# KA2_3.net
KiCad netlist of a schematic drawn in Altium Designer
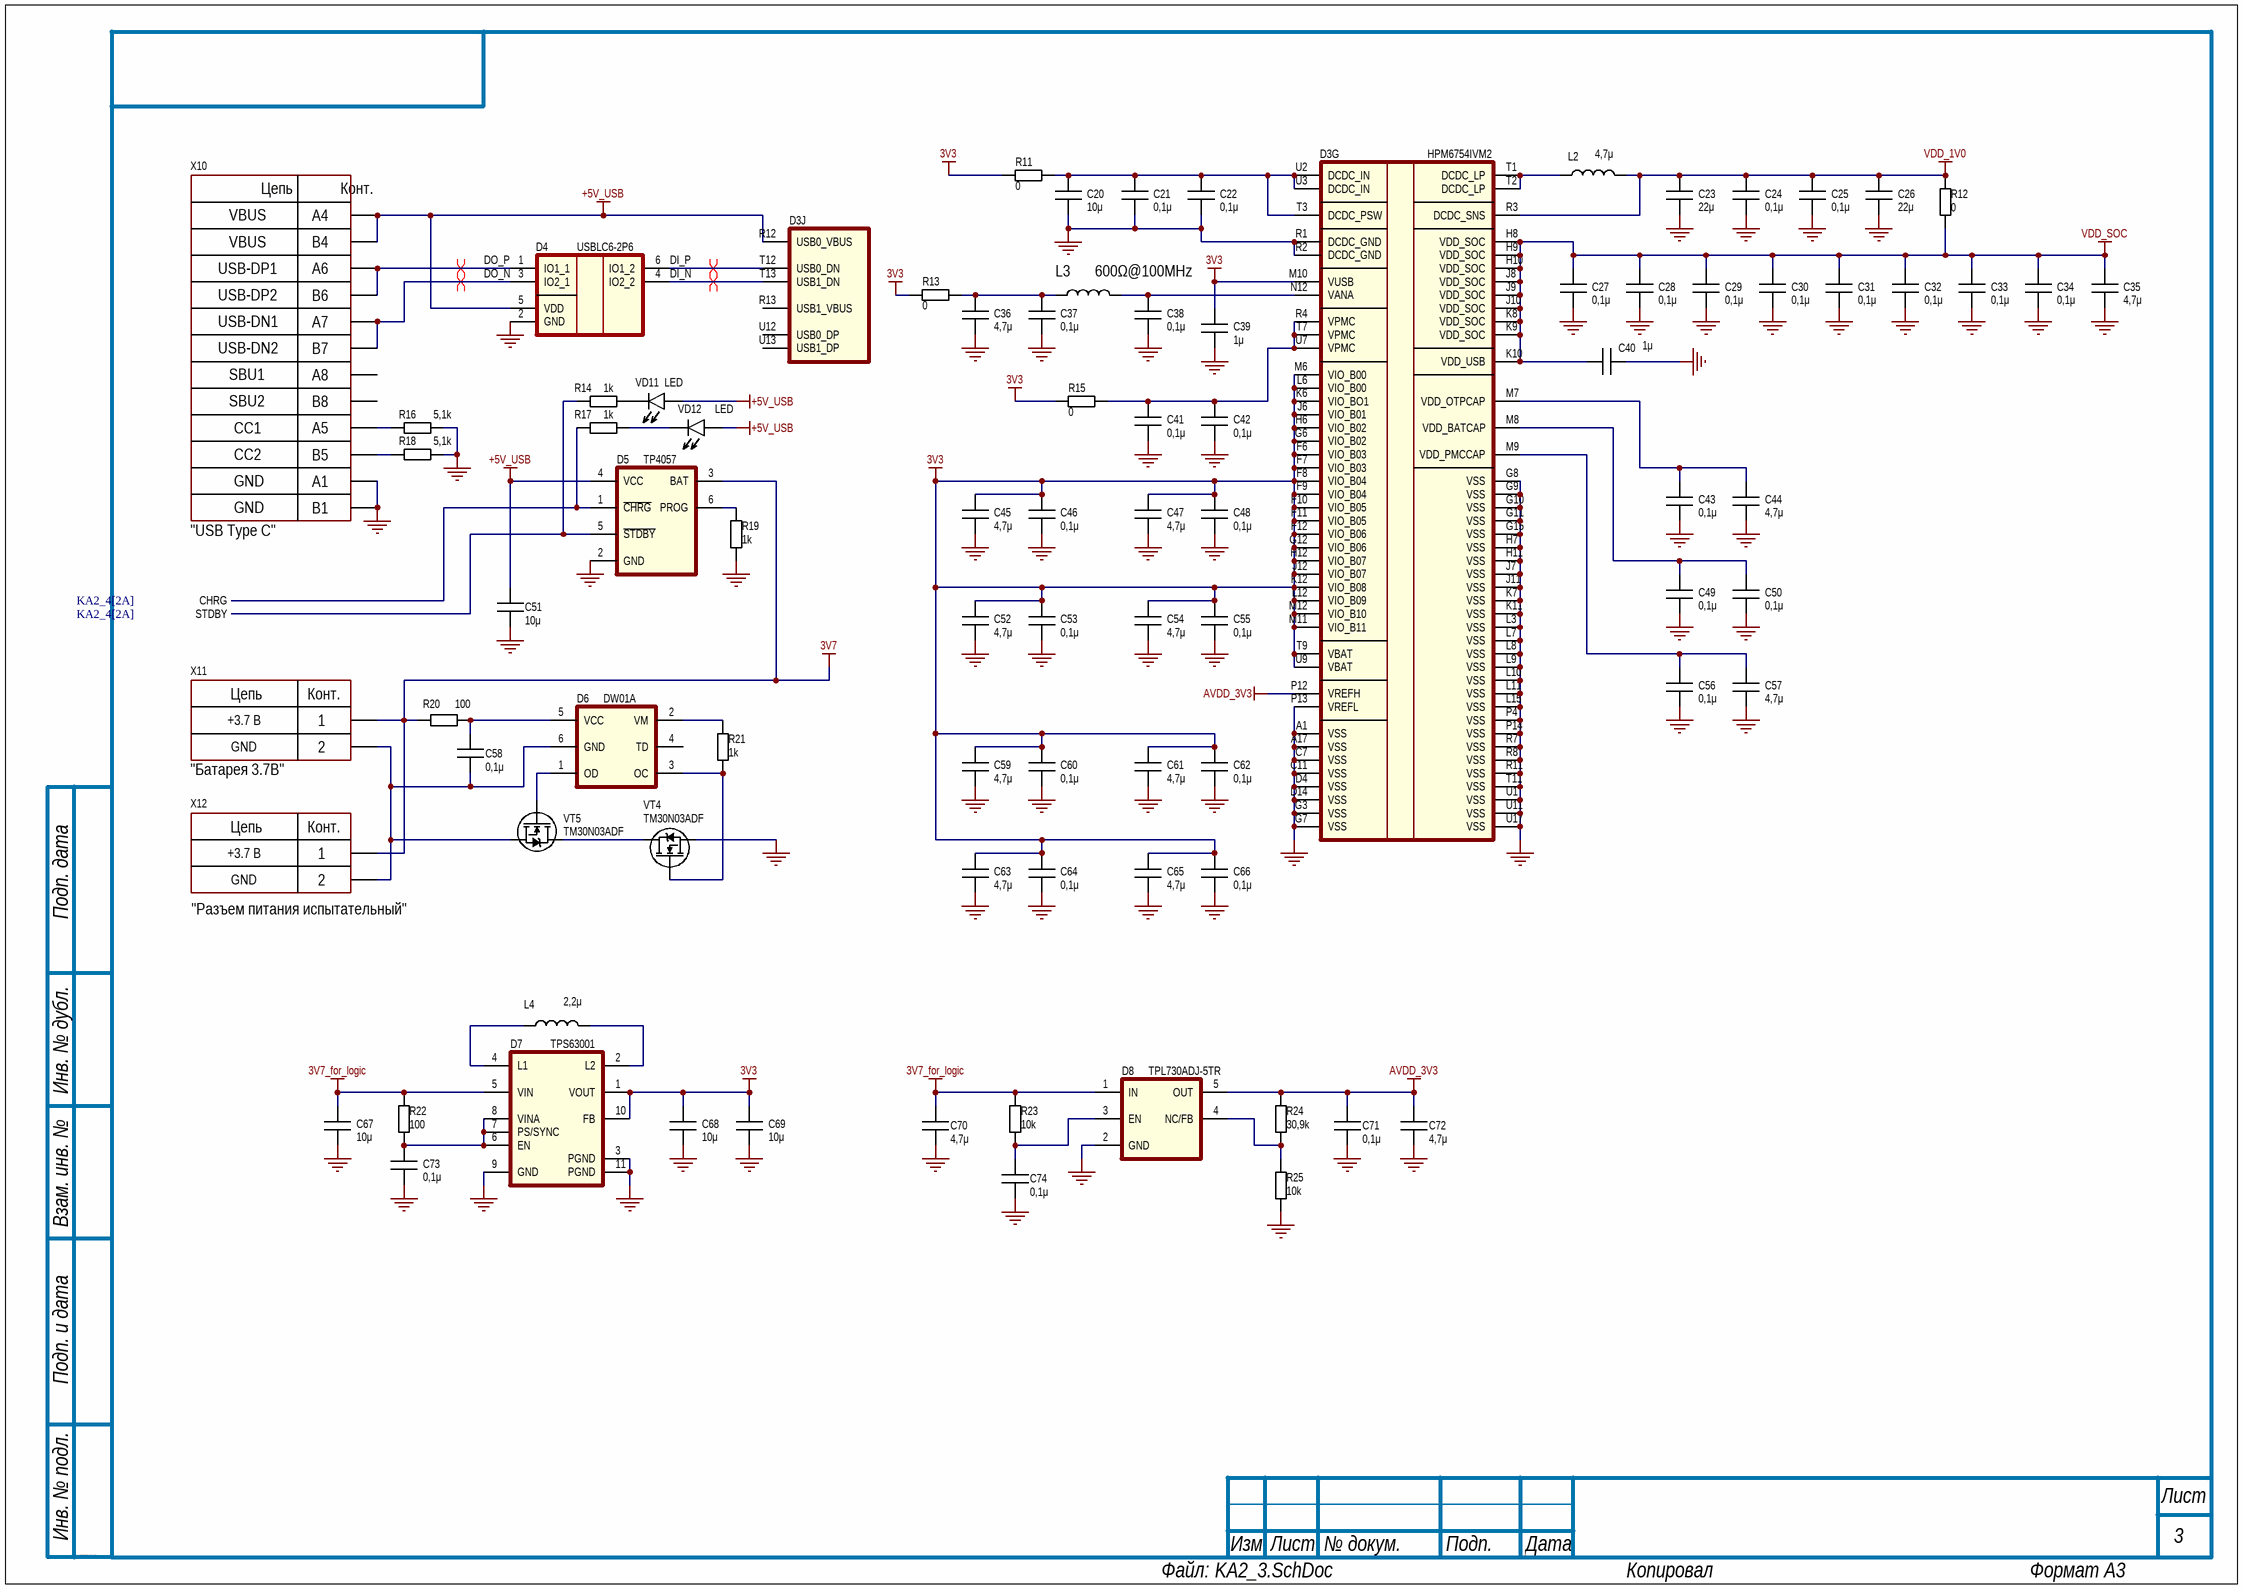
[diagram p0: KA2_3.SchDoc]

(export (version "E")
  (design (tool "Eeschema 10.0.6"))
  (components
    (comp (ref "C20")
      (value "10μ")
      (footprint "Capacitor_0402")
      (fields
        (field (name "VALUEMANUFACTURERPARTNUMBER") "Ceramic capacitor, 10μ, X7R, ±10%, 16V, 0402")
        (field (name "TOLERANCE") "±10%")
        (field (name "VOLTAGE") "16V")
      )
      (libsource (lib "Barsotion") (part "Ceramic_0402"))
    )
    (comp (ref "C21")
      (value "0,1μ")
      (footprint "Capacitor_0402")
      (fields
        (field (name "VALUEMANUFACTURERPARTNUMBER") "Ceramic capacitor, 0,1μ, X7R, ±10%, 16V, 0402")
        (field (name "TOLERANCE") "±10%")
        (field (name "VOLTAGE") "16V")
      )
      (libsource (lib "Barsotion") (part "Ceramic_0402"))
    )
    (comp (ref "C22")
      (value "0,1μ")
      (footprint "Capacitor_0402")
      (fields
        (field (name "VALUEMANUFACTURERPARTNUMBER") "Ceramic capacitor, 0,1μ, X7R, ±10%, 16V, 0402")
        (field (name "TOLERANCE") "±10%")
        (field (name "VOLTAGE") "16V")
      )
      (libsource (lib "Barsotion") (part "Ceramic_0402"))
    )
    (comp (ref "C23")
      (value "22μ")
      (footprint "Capacitor_0402")
      (fields
        (field (name "VALUEMANUFACTURERPARTNUMBER") "Ceramic capacitor, 22μ, X7R, ±10%, 16V, 0402")
        (field (name "TOLERANCE") "±10%")
        (field (name "VOLTAGE") "16V")
      )
      (libsource (lib "Barsotion") (part "Ceramic_0402"))
    )
    (comp (ref "C24")
      (value "0,1μ")
      (footprint "Capacitor_0402")
      (fields
        (field (name "VALUEMANUFACTURERPARTNUMBER") "Ceramic capacitor, 0,1μ, X7R, ±10%, 16V, 0402")
        (field (name "TOLERANCE") "±10%")
        (field (name "VOLTAGE") "16V")
      )
      (libsource (lib "Barsotion") (part "Ceramic_0402"))
    )
    (comp (ref "C25")
      (value "0,1μ")
      (footprint "Capacitor_0402")
      (fields
        (field (name "VALUEMANUFACTURERPARTNUMBER") "Ceramic capacitor, 0,1μ, X7R, ±10%, 16V, 0402")
        (field (name "TOLERANCE") "±10%")
        (field (name "VOLTAGE") "16V")
      )
      (libsource (lib "Barsotion") (part "Ceramic_0402"))
    )
    (comp (ref "C26")
      (value "22μ")
      (footprint "Capacitor_0402")
      (fields
        (field (name "VALUEMANUFACTURERPARTNUMBER") "Ceramic capacitor, 22μ, X7R, ±10%, 16V, 0402")
        (field (name "TOLERANCE") "±10%")
        (field (name "VOLTAGE") "16V")
      )
      (libsource (lib "Barsotion") (part "Ceramic_0402"))
    )
    (comp (ref "C27")
      (value "0,1μ")
      (footprint "Capacitor_0402")
      (fields
        (field (name "VALUEMANUFACTURERPARTNUMBER") "Ceramic capacitor, 0,1μ, X7R, ±10%, 16V, 0402")
        (field (name "TOLERANCE") "±10%")
        (field (name "VOLTAGE") "16V")
      )
      (libsource (lib "Barsotion") (part "Ceramic_0402"))
    )
    (comp (ref "C28")
      (value "0,1μ")
      (footprint "Capacitor_0402")
      (fields
        (field (name "VALUEMANUFACTURERPARTNUMBER") "Ceramic capacitor, 0,1μ, X7R, ±10%, 16V, 0402")
        (field (name "TOLERANCE") "±10%")
        (field (name "VOLTAGE") "16V")
      )
      (libsource (lib "Barsotion") (part "Ceramic_0402"))
    )
    (comp (ref "C29")
      (value "0,1μ")
      (footprint "Capacitor_0402")
      (fields
        (field (name "VALUEMANUFACTURERPARTNUMBER") "Ceramic capacitor, 0,1μ, X7R, ±10%, 16V, 0402")
        (field (name "TOLERANCE") "±10%")
        (field (name "VOLTAGE") "16V")
      )
      (libsource (lib "Barsotion") (part "Ceramic_0402"))
    )
    (comp (ref "C30")
      (value "0,1μ")
      (footprint "Capacitor_0402")
      (fields
        (field (name "VALUEMANUFACTURERPARTNUMBER") "Ceramic capacitor, 0,1μ, X7R, ±10%, 16V, 0402")
        (field (name "TOLERANCE") "±10%")
        (field (name "VOLTAGE") "16V")
      )
      (libsource (lib "Barsotion") (part "Ceramic_0402"))
    )
    (comp (ref "C31")
      (value "0,1μ")
      (footprint "Capacitor_0402")
      (fields
        (field (name "VALUEMANUFACTURERPARTNUMBER") "Ceramic capacitor, 0,1μ, X7R, ±10%, 16V, 0402")
        (field (name "TOLERANCE") "±10%")
        (field (name "VOLTAGE") "16V")
      )
      (libsource (lib "Barsotion") (part "Ceramic_0402"))
    )
    (comp (ref "C32")
      (value "0,1μ")
      (footprint "Capacitor_0402")
      (fields
        (field (name "VALUEMANUFACTURERPARTNUMBER") "Ceramic capacitor, 0,1μ, X7R, ±10%, 16V, 0402")
        (field (name "TOLERANCE") "±10%")
        (field (name "VOLTAGE") "16V")
      )
      (libsource (lib "Barsotion") (part "Ceramic_0402"))
    )
    (comp (ref "C33")
      (value "0,1μ")
      (footprint "Capacitor_0402")
      (fields
        (field (name "VALUEMANUFACTURERPARTNUMBER") "Ceramic capacitor, 0,1μ, X7R, ±10%, 16V, 0402")
        (field (name "TOLERANCE") "±10%")
        (field (name "VOLTAGE") "16V")
      )
      (libsource (lib "Barsotion") (part "Ceramic_0402"))
    )
    (comp (ref "C34")
      (value "0,1μ")
      (footprint "Capacitor_0402")
      (fields
        (field (name "VALUEMANUFACTURERPARTNUMBER") "Ceramic capacitor, 0,1μ, X7R, ±10%, 16V, 0402")
        (field (name "TOLERANCE") "±10%")
        (field (name "VOLTAGE") "16V")
      )
      (libsource (lib "Barsotion") (part "Ceramic_0402"))
    )
    (comp (ref "C35")
      (value "4,7μ")
      (footprint "Capacitor_0402")
      (fields
        (field (name "VALUEMANUFACTURERPARTNUMBER") "Ceramic capacitor, 4,7μ, X7R, ±10%, 16V, 0402")
        (field (name "TOLERANCE") "±10%")
        (field (name "VOLTAGE") "16V")
      )
      (libsource (lib "Barsotion") (part "Ceramic_0402"))
    )
    (comp (ref "C36")
      (value "4,7μ")
      (footprint "Capacitor_0402")
      (fields
        (field (name "VALUEMANUFACTURERPARTNUMBER") "Ceramic capacitor, 4,7μ, X7R, ±10%, 16V, 0402")
        (field (name "TOLERANCE") "±10%")
        (field (name "VOLTAGE") "16V")
      )
      (libsource (lib "Barsotion") (part "Ceramic_0402"))
    )
    (comp (ref "C37")
      (value "0,1μ")
      (footprint "Capacitor_0402")
      (fields
        (field (name "VALUEMANUFACTURERPARTNUMBER") "Ceramic capacitor, 0,1μ, X7R, ±10%, 16V, 0402")
        (field (name "TOLERANCE") "±10%")
        (field (name "VOLTAGE") "16V")
      )
      (libsource (lib "Barsotion") (part "Ceramic_0402"))
    )
    (comp (ref "C38")
      (value "0,1μ")
      (footprint "Capacitor_0402")
      (fields
        (field (name "VALUEMANUFACTURERPARTNUMBER") "Ceramic capacitor, 0,1μ, X7R, ±10%, 16V, 0402")
        (field (name "TOLERANCE") "±10%")
        (field (name "VOLTAGE") "16V")
      )
      (libsource (lib "Barsotion") (part "Ceramic_0402"))
    )
    (comp (ref "C39")
      (value "1μ")
      (footprint "Capacitor_0402")
      (fields
        (field (name "VALUEMANUFACTURERPARTNUMBER") "Ceramic capacitor, 1μ, X7R, ±10%, 16V, 0402")
        (field (name "TOLERANCE") "±10%")
        (field (name "VOLTAGE") "16V")
      )
      (libsource (lib "Barsotion") (part "Ceramic_0402"))
    )
    (comp (ref "C40")
      (value "1μ")
      (footprint "Capacitor_0402")
      (fields
        (field (name "VALUEMANUFACTURERPARTNUMBER") "Ceramic capacitor, 1μ, X7R, ±10%, 16V, 0402")
        (field (name "TOLERANCE") "±10%")
        (field (name "VOLTAGE") "16V")
      )
      (libsource (lib "Barsotion") (part "Ceramic_0402"))
    )
    (comp (ref "C41")
      (value "0,1μ")
      (footprint "Capacitor_0402")
      (fields
        (field (name "VALUEMANUFACTURERPARTNUMBER") "Ceramic capacitor, 0,1μ, X7R, ±10%, 16V, 0402")
        (field (name "TOLERANCE") "±10%")
        (field (name "VOLTAGE") "16V")
      )
      (libsource (lib "Barsotion") (part "Ceramic_0402"))
    )
    (comp (ref "C42")
      (value "0,1μ")
      (footprint "Capacitor_0402")
      (fields
        (field (name "VALUEMANUFACTURERPARTNUMBER") "Ceramic capacitor, 0,1μ, X7R, ±10%, 16V, 0402")
        (field (name "TOLERANCE") "±10%")
        (field (name "VOLTAGE") "16V")
      )
      (libsource (lib "Barsotion") (part "Ceramic_0402"))
    )
    (comp (ref "C43")
      (value "0,1μ")
      (footprint "Capacitor_0402")
      (fields
        (field (name "VALUEMANUFACTURERPARTNUMBER") "Ceramic capacitor, 0,1μ, X7R, ±10%, 16V, 0402")
        (field (name "TOLERANCE") "±10%")
        (field (name "VOLTAGE") "16V")
      )
      (libsource (lib "Barsotion") (part "Ceramic_0402"))
    )
    (comp (ref "C44")
      (value "4,7μ")
      (footprint "Capacitor_0402")
      (fields
        (field (name "VALUEMANUFACTURERPARTNUMBER") "Ceramic capacitor, 4,7μ, X7R, ±10%, 16V, 0402")
        (field (name "TOLERANCE") "±10%")
        (field (name "VOLTAGE") "16V")
      )
      (libsource (lib "Barsotion") (part "Ceramic_0402"))
    )
    (comp (ref "C45")
      (value "4,7μ")
      (footprint "Capacitor_0402")
      (fields
        (field (name "VALUEMANUFACTURERPARTNUMBER") "Ceramic capacitor, 4,7μ, X7R, ±10%, 16V, 0402")
        (field (name "TOLERANCE") "±10%")
        (field (name "VOLTAGE") "16V")
      )
      (libsource (lib "Barsotion") (part "Ceramic_0402"))
    )
    (comp (ref "C46")
      (value "0,1μ")
      (footprint "Capacitor_0402")
      (fields
        (field (name "VALUEMANUFACTURERPARTNUMBER") "Ceramic capacitor, 0,1μ, X7R, ±10%, 16V, 0402")
        (field (name "TOLERANCE") "±10%")
        (field (name "VOLTAGE") "16V")
      )
      (libsource (lib "Barsotion") (part "Ceramic_0402"))
    )
    (comp (ref "C47")
      (value "4,7μ")
      (footprint "Capacitor_0402")
      (fields
        (field (name "VALUEMANUFACTURERPARTNUMBER") "Ceramic capacitor, 4,7μ, X7R, ±10%, 16V, 0402")
        (field (name "TOLERANCE") "±10%")
        (field (name "VOLTAGE") "16V")
      )
      (libsource (lib "Barsotion") (part "Ceramic_0402"))
    )
    (comp (ref "C48")
      (value "0,1μ")
      (footprint "Capacitor_0402")
      (fields
        (field (name "VALUEMANUFACTURERPARTNUMBER") "Ceramic capacitor, 0,1μ, X7R, ±10%, 16V, 0402")
        (field (name "TOLERANCE") "±10%")
        (field (name "VOLTAGE") "16V")
      )
      (libsource (lib "Barsotion") (part "Ceramic_0402"))
    )
    (comp (ref "C49")
      (value "0,1μ")
      (footprint "Capacitor_0402")
      (fields
        (field (name "VALUEMANUFACTURERPARTNUMBER") "Ceramic capacitor, 0,1μ, X7R, ±10%, 16V, 0402")
        (field (name "TOLERANCE") "±10%")
        (field (name "VOLTAGE") "16V")
      )
      (libsource (lib "Barsotion") (part "Ceramic_0402"))
    )
    (comp (ref "C50")
      (value "0,1μ")
      (footprint "Capacitor_0402")
      (fields
        (field (name "VALUEMANUFACTURERPARTNUMBER") "Ceramic capacitor, 0,1μ, X7R, ±10%, 16V, 0402")
        (field (name "TOLERANCE") "±10%")
        (field (name "VOLTAGE") "16V")
      )
      (libsource (lib "Barsotion") (part "Ceramic_0402"))
    )
    (comp (ref "C51")
      (value "10μ")
      (footprint "Capacitor_0402")
      (fields
        (field (name "VALUEMANUFACTURERPARTNUMBER") "Ceramic capacitor, 10μ, X7R, ±10%, 16V, 0402")
        (field (name "TOLERANCE") "±10%")
        (field (name "VOLTAGE") "16V")
      )
      (libsource (lib "Barsotion") (part "Ceramic_0402"))
    )
    (comp (ref "C52")
      (value "4,7μ")
      (footprint "Capacitor_0402")
      (fields
        (field (name "VALUEMANUFACTURERPARTNUMBER") "Ceramic capacitor, 4,7μ, X7R, ±10%, 16V, 0402")
        (field (name "TOLERANCE") "±10%")
        (field (name "VOLTAGE") "16V")
      )
      (libsource (lib "Barsotion") (part "Ceramic_0402"))
    )
    (comp (ref "C53")
      (value "0,1μ")
      (footprint "Capacitor_0402")
      (fields
        (field (name "VALUEMANUFACTURERPARTNUMBER") "Ceramic capacitor, 0,1μ, X7R, ±10%, 16V, 0402")
        (field (name "TOLERANCE") "±10%")
        (field (name "VOLTAGE") "16V")
      )
      (libsource (lib "Barsotion") (part "Ceramic_0402"))
    )
    (comp (ref "C54")
      (value "4,7μ")
      (footprint "Capacitor_0402")
      (fields
        (field (name "VALUEMANUFACTURERPARTNUMBER") "Ceramic capacitor, 4,7μ, X7R, ±10%, 16V, 0402")
        (field (name "TOLERANCE") "±10%")
        (field (name "VOLTAGE") "16V")
      )
      (libsource (lib "Barsotion") (part "Ceramic_0402"))
    )
    (comp (ref "C55")
      (value "0,1μ")
      (footprint "Capacitor_0402")
      (fields
        (field (name "VALUEMANUFACTURERPARTNUMBER") "Ceramic capacitor, 0,1μ, X7R, ±10%, 16V, 0402")
        (field (name "TOLERANCE") "±10%")
        (field (name "VOLTAGE") "16V")
      )
      (libsource (lib "Barsotion") (part "Ceramic_0402"))
    )
    (comp (ref "C56")
      (value "0,1μ")
      (footprint "Capacitor_0402")
      (fields
        (field (name "VALUEMANUFACTURERPARTNUMBER") "Ceramic capacitor, 0,1μ, X7R, ±10%, 16V, 0402")
        (field (name "TOLERANCE") "±10%")
        (field (name "VOLTAGE") "16V")
      )
      (libsource (lib "Barsotion") (part "Ceramic_0402"))
    )
    (comp (ref "C57")
      (value "4,7μ")
      (footprint "Capacitor_0402")
      (fields
        (field (name "VALUEMANUFACTURERPARTNUMBER") "Ceramic capacitor, 4,7μ, X7R, ±10%, 16V, 0402")
        (field (name "TOLERANCE") "±10%")
        (field (name "VOLTAGE") "16V")
      )
      (libsource (lib "Barsotion") (part "Ceramic_0402"))
    )
    (comp (ref "C58")
      (value "0,1μ")
      (footprint "Capacitor_0402")
      (fields
        (field (name "VALUEMANUFACTURERPARTNUMBER") "Ceramic capacitor, 0,1μ, X7R, ±10%, 16V, 0402")
        (field (name "TOLERANCE") "±10%")
        (field (name "VOLTAGE") "16V")
      )
      (libsource (lib "Barsotion") (part "Ceramic_0402"))
    )
    (comp (ref "C59")
      (value "4,7μ")
      (footprint "Capacitor_0402")
      (fields
        (field (name "VALUEMANUFACTURERPARTNUMBER") "Ceramic capacitor, 4,7μ, X7R, ±10%, 16V, 0402")
        (field (name "TOLERANCE") "±10%")
        (field (name "VOLTAGE") "16V")
      )
      (libsource (lib "Barsotion") (part "Ceramic_0402"))
    )
    (comp (ref "C60")
      (value "0,1μ")
      (footprint "Capacitor_0402")
      (fields
        (field (name "VALUEMANUFACTURERPARTNUMBER") "Ceramic capacitor, 0,1μ, X7R, ±10%, 16V, 0402")
        (field (name "TOLERANCE") "±10%")
        (field (name "VOLTAGE") "16V")
      )
      (libsource (lib "Barsotion") (part "Ceramic_0402"))
    )
    (comp (ref "C61")
      (value "4,7μ")
      (footprint "Capacitor_0402")
      (fields
        (field (name "VALUEMANUFACTURERPARTNUMBER") "Ceramic capacitor, 4,7μ, X7R, ±10%, 16V, 0402")
        (field (name "TOLERANCE") "±10%")
        (field (name "VOLTAGE") "16V")
      )
      (libsource (lib "Barsotion") (part "Ceramic_0402"))
    )
    (comp (ref "C62")
      (value "0,1μ")
      (footprint "Capacitor_0402")
      (fields
        (field (name "VALUEMANUFACTURERPARTNUMBER") "Ceramic capacitor, 0,1μ, X7R, ±10%, 16V, 0402")
        (field (name "TOLERANCE") "±10%")
        (field (name "VOLTAGE") "16V")
      )
      (libsource (lib "Barsotion") (part "Ceramic_0402"))
    )
    (comp (ref "C63")
      (value "4,7μ")
      (footprint "Capacitor_0402")
      (fields
        (field (name "VALUEMANUFACTURERPARTNUMBER") "Ceramic capacitor, 4,7μ, X7R, ±10%, 16V, 0402")
        (field (name "TOLERANCE") "±10%")
        (field (name "VOLTAGE") "16V")
      )
      (libsource (lib "Barsotion") (part "Ceramic_0402"))
    )
    (comp (ref "C64")
      (value "0,1μ")
      (footprint "Capacitor_0402")
      (fields
        (field (name "VALUEMANUFACTURERPARTNUMBER") "Ceramic capacitor, 0,1μ, X7R, ±10%, 16V, 0402")
        (field (name "TOLERANCE") "±10%")
        (field (name "VOLTAGE") "16V")
      )
      (libsource (lib "Barsotion") (part "Ceramic_0402"))
    )
    (comp (ref "C65")
      (value "4,7μ")
      (footprint "Capacitor_0402")
      (fields
        (field (name "VALUEMANUFACTURERPARTNUMBER") "Ceramic capacitor, 4,7μ, X7R, ±10%, 16V, 0402")
        (field (name "TOLERANCE") "±10%")
        (field (name "VOLTAGE") "16V")
      )
      (libsource (lib "Barsotion") (part "Ceramic_0402"))
    )
    (comp (ref "C66")
      (value "0,1μ")
      (footprint "Capacitor_0402")
      (fields
        (field (name "VALUEMANUFACTURERPARTNUMBER") "Ceramic capacitor, 0,1μ, X7R, ±10%, 16V, 0402")
        (field (name "TOLERANCE") "±10%")
        (field (name "VOLTAGE") "16V")
      )
      (libsource (lib "Barsotion") (part "Ceramic_0402"))
    )
    (comp (ref "C67")
      (value "10μ")
      (footprint "Capacitor_0402")
      (fields
        (field (name "VALUEMANUFACTURERPARTNUMBER") "Ceramic capacitor, 10μ, X7R, ±10%, 16V, 0402")
        (field (name "TOLERANCE") "±10%")
        (field (name "VOLTAGE") "16V")
      )
      (libsource (lib "Barsotion") (part "Ceramic_0402"))
    )
    (comp (ref "C68")
      (value "10μ")
      (footprint "Capacitor_0402")
      (fields
        (field (name "VALUEMANUFACTURERPARTNUMBER") "Ceramic capacitor, 10μ, X7R, ±10%, 16V, 0402")
        (field (name "TOLERANCE") "±10%")
        (field (name "VOLTAGE") "16V")
      )
      (libsource (lib "Barsotion") (part "Ceramic_0402"))
    )
    (comp (ref "C69")
      (value "10μ")
      (footprint "Capacitor_0402")
      (fields
        (field (name "VALUEMANUFACTURERPARTNUMBER") "Ceramic capacitor, 10μ, X7R, ±10%, 16V, 0402")
        (field (name "TOLERANCE") "±10%")
        (field (name "VOLTAGE") "16V")
      )
      (libsource (lib "Barsotion") (part "Ceramic_0402"))
    )
    (comp (ref "C70")
      (value "4,7μ")
      (footprint "Capacitor_0402")
      (fields
        (field (name "VALUEMANUFACTURERPARTNUMBER") "Ceramic capacitor, 4,7μ, X7R, ±10%, 16V, 0402")
        (field (name "TOLERANCE") "±10%")
        (field (name "VOLTAGE") "16V")
      )
      (libsource (lib "Barsotion") (part "Ceramic_0402"))
    )
    (comp (ref "C71")
      (value "0,1μ")
      (footprint "Capacitor_0402")
      (fields
        (field (name "VALUEMANUFACTURERPARTNUMBER") "Ceramic capacitor, 0,1μ, X7R, ±10%, 16V, 0402")
        (field (name "TOLERANCE") "±10%")
        (field (name "VOLTAGE") "16V")
      )
      (libsource (lib "Barsotion") (part "Ceramic_0402"))
    )
    (comp (ref "C72")
      (value "4,7μ")
      (footprint "Capacitor_0402")
      (fields
        (field (name "VALUEMANUFACTURERPARTNUMBER") "Ceramic capacitor, 4,7μ, X7R, ±10%, 16V, 0402")
        (field (name "TOLERANCE") "±10%")
        (field (name "VOLTAGE") "16V")
      )
      (libsource (lib "Barsotion") (part "Ceramic_0402"))
    )
    (comp (ref "C73")
      (value "0,1μ")
      (footprint "Capacitor_0402")
      (fields
        (field (name "VALUEMANUFACTURERPARTNUMBER") "Ceramic capacitor, 0,1μ, X7R, ±10%, 16V, 0402")
        (field (name "TOLERANCE") "±10%")
        (field (name "VOLTAGE") "16V")
      )
      (libsource (lib "Barsotion") (part "Ceramic_0402"))
    )
    (comp (ref "C74")
      (value "0,1μ")
      (footprint "Capacitor_0402")
      (fields
        (field (name "VALUEMANUFACTURERPARTNUMBER") "Ceramic capacitor, 0,1μ, X7R, ±10%, 16V, 0402")
        (field (name "TOLERANCE") "±10%")
        (field (name "VOLTAGE") "16V")
      )
      (libsource (lib "Barsotion") (part "Ceramic_0402"))
    )
    (comp (ref "D3")
      (value "HPM6754IVM2")
      (footprint "HPM6754IVM2_BGA-289_14x14mm")
      (description "Микроконтроллер RISC-V, 2xRV32GCBP@816МГц, 2МБ ОЗУ, BGA-289 14x14mm")
      (fields (field (name "MANUFACTURER") "HPMICRO"))
      (libsource (lib "") (part "HPM6754IVM2_1"))
    )
    (comp (ref "D4")
      (value "USBLC6-2P6")
      (footprint "SOT-666")
      (description "Микросхема защиты USB от статики, SOT-666")
      (fields (field (name "MANUFACTURER") "STMicroelectronics"))
      (libsource (lib "Barsotion") (part "USBLC6-2P6"))
    )
    (comp (ref "D5")
      (value "TP4057")
      (footprint "SOT23-6")
      (description "Микросхема зарядки li-ion барареи, SOT-23-6")
      (fields (field (name "MANUFACTURER") "JSMSEMI"))
      (libsource (lib "Barsotion") (part "TP4057"))
    )
    (comp (ref "D6")
      (value "DW01A")
      (footprint "SOT23-6")
      (description "Микросхема защиты li-ion-батареи")
      (fields (field (name "MFR.PART") "DW01A-JSM") (field (name "MANUFACTURER") "JSMSEMI"))
      (libsource (lib "Barsotion") (part "DW01A"))
    )
    (comp (ref "D7")
      (value "TPS63001")
      (footprint "TPS6300x")
      (description "Микросхема драйвера повышающе-понижающего преобразователя, вход 1,8...5,5В, выход 3,3В, 800-1200мА")
      (fields (field (name "MFR.PART") "TPS63001DRCR") (field (name "MANUFACTURER") "Texas Instruments"))
      (libsource (lib "Barsotion") (part "TPS63001"))
    )
    (comp (ref "D8")
      (value "TPL730ADJ-5TR")
      (footprint "SOT-23-5")
      (description "Микросхема драйвера импульсного понижающего преобразователя")
      (fields (field (name "MANUFACTURER") "3PEAK") (field (name "Comment") "TPL730ADJ-5TL"))
      (libsource (lib "Barsotion") (part "TPL730ADJ-5TL"))
    )
    (comp (ref "L2")
      (value "4,7μ")
      (footprint "Inductor_1008")
      (description "1.55A 4.7uH ±20% 1.9A 196mΩ Magnetic Shielded Inductor 1008 Fixed Inductors RoHS")
      (fields (field (name "MFR.PART") "FWP252012P-4R7ML") (field (name "MANUFACTURER") "cjiang"))
      (libsource (lib "Barsotion") (part "Inductor_FWP252012P-4R7ML"))
    )
    (comp (ref "L3")
      (value "600Ω@100MHz")
      (footprint "IND: 0603")
      (fields
        (field (name "TOLERANCE") "±10%")
        (field (name "VALUEMANUFACTURERPARTNUMBER") "Inductor, 600Ω@100MHz, ±10%, 0603")
      )
      (libsource (lib "Barsotion") (part "Inductor_0603"))
    )
    (comp (ref "L4")
      (value "2,2μ")
      (footprint "Inductor_1008")
      (description "3A 2.2uH ±20% 55mΩ 3.8A 1008 Fixed Inductors RoHS")
      (fields (field (name "MFR.PART") "FTC252012S2R2MBCA") (field (name "MANUFACTURER") "cjiang"))
      (libsource (lib "Barsotion") (part "Inductor_FTC252012S2R2MBCA"))
    )
    (comp (ref "R11")
      (value "0")
      (footprint "RES: 0805")
      (fields
        (field (name "VALUEMANUFACTURERPARTNUMBER") "Resistor, 0, ±1%, 0805")
        (field (name "TOLERANCE") "±1%")
      )
      (libsource (lib "Barsotion") (part "Resistor_0805"))
    )
    (comp (ref "R12")
      (value "0")
      (footprint "RES: 0805")
      (fields
        (field (name "VALUEMANUFACTURERPARTNUMBER") "Resistor, 0, ±1%, 0805")
        (field (name "TOLERANCE") "±1%")
      )
      (libsource (lib "") (part "Resistor_0805_1"))
    )
    (comp (ref "R13")
      (value "0")
      (footprint "RES: 0805")
      (fields
        (field (name "VALUEMANUFACTURERPARTNUMBER") "Resistor, 0, ±1%, 0805")
        (field (name "TOLERANCE") "±1%")
      )
      (libsource (lib "Barsotion") (part "Resistor_0805"))
    )
    (comp (ref "R14")
      (value "1k")
      (footprint "RES: 0402")
      (fields
        (field (name "VALUEMANUFACTURERPARTNUMBER") "Resistor, 1k, ±1%, 0402")
        (field (name "TOLERANCE") "±1%")
      )
      (libsource (lib "Barsotion") (part "Resistor_0402"))
    )
    (comp (ref "R15")
      (value "0")
      (footprint "RES: 0805")
      (fields
        (field (name "VALUEMANUFACTURERPARTNUMBER") "Resistor, 0, ±1%, 0805")
        (field (name "TOLERANCE") "±1%")
      )
      (libsource (lib "Barsotion") (part "Resistor_0805"))
    )
    (comp (ref "R16")
      (value "5,1k")
      (footprint "RES: 0402")
      (fields
        (field (name "VALUEMANUFACTURERPARTNUMBER") "Resistor, 5,1k, ±1%, 0402")
        (field (name "TOLERANCE") "±1%")
      )
      (libsource (lib "Barsotion") (part "Resistor_0402"))
    )
    (comp (ref "R17")
      (value "1k")
      (footprint "RES: 0402")
      (fields
        (field (name "VALUEMANUFACTURERPARTNUMBER") "Resistor, 1k, ±1%, 0402")
        (field (name "TOLERANCE") "±1%")
      )
      (libsource (lib "Barsotion") (part "Resistor_0402"))
    )
    (comp (ref "R18")
      (value "5,1k")
      (footprint "RES: 0402")
      (fields
        (field (name "VALUEMANUFACTURERPARTNUMBER") "Resistor, 5,1k, ±1%, 0402")
        (field (name "TOLERANCE") "±1%")
      )
      (libsource (lib "Barsotion") (part "Resistor_0402"))
    )
    (comp (ref "R19")
      (value "1k")
      (footprint "RES: 0402")
      (fields
        (field (name "MANUFACTURER") "Yageo")
        (field (name "TOLERANCE") "±1%")
        (field (name "VALUEMANUFACTURERPARTNUMBER") "Resistor, 1k, ±1%, 0402")
      )
      (libsource (lib "") (part "Resistor_0402_1"))
    )
    (comp (ref "R20")
      (value "100")
      (footprint "RES: 0402")
      (fields
        (field (name "VALUEMANUFACTURERPARTNUMBER") "Resistor, 100, ±1%, 0402")
        (field (name "TOLERANCE") "±1%")
      )
      (libsource (lib "Barsotion") (part "Resistor_0402"))
    )
    (comp (ref "R21")
      (value "1k")
      (footprint "RES: 0402")
      (fields
        (field (name "VALUEMANUFACTURERPARTNUMBER") "Resistor, 1k, ±1%, 0402")
        (field (name "TOLERANCE") "±1%")
      )
      (libsource (lib "") (part "Resistor_0402_1"))
    )
    (comp (ref "R22")
      (value "100")
      (footprint "RES: 0805")
      (fields
        (field (name "VALUEMANUFACTURERPARTNUMBER") "Resistor, 100, ±1%, 0805")
        (field (name "TOLERANCE") "±1%")
      )
      (libsource (lib "") (part "Resistor_0805_2"))
    )
    (comp (ref "R23")
      (value "10k")
      (footprint "RES: 0402")
      (fields
        (field (name "VALUEMANUFACTURERPARTNUMBER") "Resistor, 10k, ±1%, 0402")
        (field (name "TOLERANCE") "±1%")
      )
      (libsource (lib "") (part "Resistor_0402_1"))
    )
    (comp (ref "R24")
      (value "30,9k")
      (footprint "RES: 0402")
      (fields
        (field (name "VALUEMANUFACTURERPARTNUMBER") "Resistor, 30,9k, ±1%, 0402")
        (field (name "TOLERANCE") "±1%")
      )
      (libsource (lib "") (part "Resistor_0402_1"))
    )
    (comp (ref "R25")
      (value "10k")
      (footprint "RES: 0402")
      (fields
        (field (name "VALUEMANUFACTURERPARTNUMBER") "Resistor, 10k, ±1%, 0402")
        (field (name "TOLERANCE") "±1%")
      )
      (libsource (lib "") (part "Resistor_0402_1"))
    )
    (comp (ref "VD11")
      (value "LED")
      (footprint "LED: 0603Y")
      (description "Светодиод желтый, 0603")
      (fields (field (name "MFR.PART") "TJ-S1608CY6T5ALC9Y-A5") (field (name "MANUFACTURER") "TOGIALED"))
      (libsource (lib "Barsotion") (part "LED_0603_Y"))
    )
    (comp (ref "VD12")
      (value "LED")
      (footprint "LED: 0603Y")
      (description "Светодиод красный, 0603")
      (fields (field (name "MFR.PART") "XL-1608SURC-06") (field (name "MANUFACTURER") "XINGLIGHT"))
      (libsource (lib "Barsotion") (part "LED_0603_R"))
    )
    (comp (ref "VT4")
      (value "TM30N03ADF")
      (footprint "TM30N03ADF")
      (description "Транзистор N-канальный, 30В 30А 15Вт, DFN3x3-8")
      (fields (field (name "MANUFACTURER") "Tritech-MOS"))
      (libsource (lib "Barsotion") (part "TM30N03ADF"))
    )
    (comp (ref "VT5")
      (value "TM30N03ADF")
      (footprint "TM30N03ADF")
      (description "Транзистор N-канальный, 30В 30А 15Вт, DFN3x3-8")
      (fields (field (name "MANUFACTURER") "Tritech-MOS"))
      (libsource (lib "Barsotion") (part "TM30N03ADF"))
    )
    (comp (ref "X10")
      (value "USB-C (USB TYPE-C) Receptacle Connector 16 Position Surface Mount")
      (footprint "CON: TYPE-C-31-M-12")
      (description "16-pin USB-C connector, surface mount")
      (fields
        (field (name "MANUFACTURER") "HDGC")
        (field (name "COMMENTTEXT") "\"USB Type C\"")
        (field (name "MFR.PART") "TYPE C-DB-116PWB")
      )
      (libsource (lib "Barsotion") (part "Connector_USB_Type_C"))
    )
    (comp (ref "X11")
      (value "\"Батарея 3.7В\"")
      (footprint "CONN_BATTERY_3V7_V2")
      (libsource (lib "Barsotion") (part "Connector_Battery"))
    )
    (comp (ref "X12")
      (value "\"Разъем питания испытательный\"")
      (footprint "CONN_JST_XH_B2B-XH-A_1x02_P2.50mm")
      (libsource (lib "Barsotion") (part "Connector_JST_XH_B2B-XH-A_1x02_2.50mm"))
    )
  )
  (nets
    (net (code "1") (name "+5V_USB") (class "Default")
      (node (ref "C51") (pin "2") (pinfunction "2_2") (pintype "passive"))
      (node (ref "D3") (pin "R12") (pinfunction "USB0_VBUS_R12") (pintype "passive"))
      (node (ref "D4") (pin "5") (pinfunction "VDD_5") (pintype "passive"))
      (node (ref "D5") (pin "4") (pinfunction "VCC_4") (pintype "passive"))
      (node (ref "VD11") (pin "A") (pinfunction "Anode_A") (pintype "passive"))
      (node (ref "VD12") (pin "A") (pinfunction "Anode_A") (pintype "passive"))
      (node (ref "X10") (pin "A4") (pinfunction "A4_A4") (pintype "passive"))
      (node (ref "X10") (pin "B4") (pinfunction "B4_B4") (pintype "passive"))
    )
    (net (code "2") (name "/CHRG") (class "Default")
      (node (ref "D5") (pin "1") (pinfunction "~{CHRG}_1") (pintype "passive"))
      (node (ref "R17") (pin "1") (pinfunction "1_1") (pintype "passive"))
    )
    (net (code "3") (name "/DI_N") (class "Default")
      (node (ref "D3") (pin "T13") (pinfunction "USB1_DN_T13") (pintype "passive"))
      (node (ref "D4") (pin "4") (pinfunction "IO2_2_4") (pintype "passive"))
    )
    (net (code "4") (name "/DI_P") (class "Default")
      (node (ref "D3") (pin "T12") (pinfunction "USB0_DN_T12") (pintype "passive"))
      (node (ref "D4") (pin "6") (pinfunction "IO1_2_6") (pintype "passive"))
    )
    (net (code "5") (name "/DO_N") (class "Default")
      (node (ref "D4") (pin "3") (pinfunction "IO2_1_3") (pintype "passive"))
      (node (ref "X10") (pin "A7") (pinfunction "A7_A7") (pintype "power_in"))
      (node (ref "X10") (pin "B7") (pinfunction "B7_B7") (pintype "power_in"))
    )
    (net (code "6") (name "/DO_P") (class "Default")
      (node (ref "D4") (pin "1") (pinfunction "IO1_1_1") (pintype "passive"))
      (node (ref "X10") (pin "A6") (pinfunction "A6_A6") (pintype "power_in"))
      (node (ref "X10") (pin "B6") (pinfunction "B6_B6") (pintype "power_in"))
    )
    (net (code "7") (name "/STDBY") (class "Default")
      (node (ref "D5") (pin "5") (pinfunction "~{STDBY}_5") (pintype "passive"))
      (node (ref "R14") (pin "1") (pinfunction "1_1") (pintype "passive"))
    )
    (net (code "8") (name "3V3") (class "Default")
      (node (ref "C39") (pin "2") (pinfunction "2_2") (pintype "passive"))
      (node (ref "C45") (pin "2") (pinfunction "2_2") (pintype "passive"))
      (node (ref "C46") (pin "2") (pinfunction "2_2") (pintype "passive"))
      (node (ref "C47") (pin "2") (pinfunction "2_2") (pintype "passive"))
      (node (ref "C48") (pin "2") (pinfunction "2_2") (pintype "passive"))
      (node (ref "C52") (pin "2") (pinfunction "2_2") (pintype "passive"))
      (node (ref "C53") (pin "2") (pinfunction "2_2") (pintype "passive"))
      (node (ref "C54") (pin "2") (pinfunction "2_2") (pintype "passive"))
      (node (ref "C55") (pin "2") (pinfunction "2_2") (pintype "passive"))
      (node (ref "C59") (pin "2") (pinfunction "2_2") (pintype "passive"))
      (node (ref "C60") (pin "2") (pinfunction "2_2") (pintype "passive"))
      (node (ref "C61") (pin "2") (pinfunction "2_2") (pintype "passive"))
      (node (ref "C62") (pin "2") (pinfunction "2_2") (pintype "passive"))
      (node (ref "C63") (pin "2") (pinfunction "2_2") (pintype "passive"))
      (node (ref "C64") (pin "2") (pinfunction "2_2") (pintype "passive"))
      (node (ref "C65") (pin "2") (pinfunction "2_2") (pintype "passive"))
      (node (ref "C66") (pin "2") (pinfunction "2_2") (pintype "passive"))
      (node (ref "C68") (pin "2") (pinfunction "2_2") (pintype "passive"))
      (node (ref "C69") (pin "2") (pinfunction "2_2") (pintype "passive"))
      (node (ref "D3") (pin "F10") (pinfunction "VIO_B05_F10") (pintype "power_in"))
      (node (ref "D3") (pin "F11") (pinfunction "VIO_B05_F11") (pintype "power_in"))
      (node (ref "D3") (pin "F12") (pinfunction "VIO_B06_F12") (pintype "power_in"))
      (node (ref "D3") (pin "F6") (pinfunction "VIO_B03_F6") (pintype "power_in"))
      (node (ref "D3") (pin "F7") (pinfunction "VIO_B03_F7") (pintype "power_in"))
      (node (ref "D3") (pin "F8") (pinfunction "VIO_B04_F8") (pintype "power_in"))
      (node (ref "D3") (pin "F9") (pinfunction "VIO_B04_F9") (pintype "power_in"))
      (node (ref "D3") (pin "G12") (pinfunction "VIO_B06_G12") (pintype "power_in"))
      (node (ref "D3") (pin "G6") (pinfunction "VIO_B02_G6") (pintype "power_in"))
      (node (ref "D3") (pin "H12") (pinfunction "VIO_B07_H12") (pintype "power_in"))
      (node (ref "D3") (pin "H6") (pinfunction "VIO_B02_H6") (pintype "power_in"))
      (node (ref "D3") (pin "J12") (pinfunction "VIO_B07_J12") (pintype "power_in"))
      (node (ref "D3") (pin "J6") (pinfunction "VIO_B01_J6") (pintype "power_in"))
      (node (ref "D3") (pin "K12") (pinfunction "VIO_B08_K12") (pintype "power_in"))
      (node (ref "D3") (pin "K6") (pinfunction "VIO_BO1_K6") (pintype "power_in"))
      (node (ref "D3") (pin "L12") (pinfunction "VIO_B09_L12") (pintype "power_in"))
      (node (ref "D3") (pin "L6") (pinfunction "VIO_B00_L6") (pintype "power_in"))
      (node (ref "D3") (pin "M10") (pinfunction "VUSB_M10") (pintype "power_in"))
      (node (ref "D3") (pin "M11") (pinfunction "VIO_B11_M11") (pintype "power_in"))
      (node (ref "D3") (pin "M12") (pinfunction "VIO_B10_M12") (pintype "power_in"))
      (node (ref "D3") (pin "M6") (pinfunction "VIO_B00_M6") (pintype "power_in"))
      (node (ref "D3") (pin "T9") (pinfunction "VBAT_T9") (pintype "power_in"))
      (node (ref "D3") (pin "U9") (pinfunction "VBAT_U9") (pintype "power_in"))
      (node (ref "D7") (pin "1") (pinfunction "VOUT_1") (pintype "passive"))
      (node (ref "D7") (pin "10") (pinfunction "FB_10") (pintype "passive"))
      (node (ref "R11") (pin "2") (pinfunction "2_2") (pintype "passive"))
      (node (ref "R13") (pin "2") (pinfunction "2_2") (pintype "passive"))
      (node (ref "R15") (pin "2") (pinfunction "2_2") (pintype "passive"))
    )
    (net (code "9") (name "3V7") (class "Default")
      (node (ref "D5") (pin "3") (pinfunction "BAT_3") (pintype "passive"))
      (node (ref "R20") (pin "1") (pinfunction "1_1") (pintype "passive"))
      (node (ref "X11") (pin "1") (pinfunction "1_1") (pintype "passive"))
      (node (ref "X12") (pin "1") (pinfunction "1_1") (pintype "passive"))
    )
    (net (code "10") (name "3V7_for_logic") (class "Default")
      (node (ref "C67") (pin "2") (pinfunction "2_2") (pintype "passive"))
      (node (ref "C70") (pin "2") (pinfunction "2_2") (pintype "passive"))
      (node (ref "D7") (pin "5") (pinfunction "VIN_5") (pintype "passive"))
      (node (ref "D8") (pin "1") (pinfunction "IN_1") (pintype "passive"))
      (node (ref "R22") (pin "1") (pinfunction "1_1") (pintype "passive"))
      (node (ref "R23") (pin "2") (pinfunction "2_2") (pintype "passive"))
    )
    (net (code "11") (name "AVDD_3V3") (class "Default")
      (node (ref "C71") (pin "2") (pinfunction "2_2") (pintype "passive"))
      (node (ref "C72") (pin "2") (pinfunction "2_2") (pintype "passive"))
      (node (ref "D3") (pin "P12") (pinfunction "VREFH_P12") (pintype "passive"))
      (node (ref "D8") (pin "5") (pinfunction "OUT_5") (pintype "passive"))
      (node (ref "R24") (pin "2") (pinfunction "2_2") (pintype "passive"))
    )
    (net (code "12") (name "GND") (class "Default")
      (node (ref "C20") (pin "1") (pinfunction "1_1") (pintype "passive"))
      (node (ref "C21") (pin "1") (pinfunction "1_1") (pintype "passive"))
      (node (ref "C22") (pin "1") (pinfunction "1_1") (pintype "passive"))
      (node (ref "C23") (pin "1") (pinfunction "1_1") (pintype "passive"))
      (node (ref "C24") (pin "1") (pinfunction "1_1") (pintype "passive"))
      (node (ref "C25") (pin "1") (pinfunction "1_1") (pintype "passive"))
      (node (ref "C26") (pin "1") (pinfunction "1_1") (pintype "passive"))
      (node (ref "C27") (pin "1") (pinfunction "1_1") (pintype "passive"))
      (node (ref "C28") (pin "1") (pinfunction "1_1") (pintype "passive"))
      (node (ref "C29") (pin "1") (pinfunction "1_1") (pintype "passive"))
      (node (ref "C30") (pin "1") (pinfunction "1_1") (pintype "passive"))
      (node (ref "C31") (pin "1") (pinfunction "1_1") (pintype "passive"))
      (node (ref "C32") (pin "1") (pinfunction "1_1") (pintype "passive"))
      (node (ref "C33") (pin "1") (pinfunction "1_1") (pintype "passive"))
      (node (ref "C34") (pin "1") (pinfunction "1_1") (pintype "passive"))
      (node (ref "C35") (pin "1") (pinfunction "1_1") (pintype "passive"))
      (node (ref "C36") (pin "1") (pinfunction "1_1") (pintype "passive"))
      (node (ref "C37") (pin "1") (pinfunction "1_1") (pintype "passive"))
      (node (ref "C38") (pin "1") (pinfunction "1_1") (pintype "passive"))
      (node (ref "C39") (pin "1") (pinfunction "1_1") (pintype "passive"))
      (node (ref "C40") (pin "1") (pinfunction "1_1") (pintype "passive"))
      (node (ref "C41") (pin "1") (pinfunction "1_1") (pintype "passive"))
      (node (ref "C42") (pin "1") (pinfunction "1_1") (pintype "passive"))
      (node (ref "C43") (pin "1") (pinfunction "1_1") (pintype "passive"))
      (node (ref "C44") (pin "1") (pinfunction "1_1") (pintype "passive"))
      (node (ref "C45") (pin "1") (pinfunction "1_1") (pintype "passive"))
      (node (ref "C46") (pin "1") (pinfunction "1_1") (pintype "passive"))
      (node (ref "C47") (pin "1") (pinfunction "1_1") (pintype "passive"))
      (node (ref "C48") (pin "1") (pinfunction "1_1") (pintype "passive"))
      (node (ref "C49") (pin "1") (pinfunction "1_1") (pintype "passive"))
      (node (ref "C50") (pin "1") (pinfunction "1_1") (pintype "passive"))
      (node (ref "C51") (pin "1") (pinfunction "1_1") (pintype "passive"))
      (node (ref "C52") (pin "1") (pinfunction "1_1") (pintype "passive"))
      (node (ref "C53") (pin "1") (pinfunction "1_1") (pintype "passive"))
      (node (ref "C54") (pin "1") (pinfunction "1_1") (pintype "passive"))
      (node (ref "C55") (pin "1") (pinfunction "1_1") (pintype "passive"))
      (node (ref "C56") (pin "1") (pinfunction "1_1") (pintype "passive"))
      (node (ref "C57") (pin "1") (pinfunction "1_1") (pintype "passive"))
      (node (ref "C59") (pin "1") (pinfunction "1_1") (pintype "passive"))
      (node (ref "C60") (pin "1") (pinfunction "1_1") (pintype "passive"))
      (node (ref "C61") (pin "1") (pinfunction "1_1") (pintype "passive"))
      (node (ref "C62") (pin "1") (pinfunction "1_1") (pintype "passive"))
      (node (ref "C63") (pin "1") (pinfunction "1_1") (pintype "passive"))
      (node (ref "C64") (pin "1") (pinfunction "1_1") (pintype "passive"))
      (node (ref "C65") (pin "1") (pinfunction "1_1") (pintype "passive"))
      (node (ref "C66") (pin "1") (pinfunction "1_1") (pintype "passive"))
      (node (ref "C67") (pin "1") (pinfunction "1_1") (pintype "passive"))
      (node (ref "C68") (pin "1") (pinfunction "1_1") (pintype "passive"))
      (node (ref "C69") (pin "1") (pinfunction "1_1") (pintype "passive"))
      (node (ref "C70") (pin "1") (pinfunction "1_1") (pintype "passive"))
      (node (ref "C71") (pin "1") (pinfunction "1_1") (pintype "passive"))
      (node (ref "C72") (pin "1") (pinfunction "1_1") (pintype "passive"))
      (node (ref "C73") (pin "1") (pinfunction "1_1") (pintype "passive"))
      (node (ref "C74") (pin "1") (pinfunction "1_1") (pintype "passive"))
      (node (ref "D3") (pin "A1") (pinfunction "VSS_A1") (pintype "power_in"))
      (node (ref "D3") (pin "A17") (pinfunction "VSS_A17") (pintype "passive"))
      (node (ref "D3") (pin "C11") (pinfunction "VSS_C11") (pintype "passive"))
      (node (ref "D3") (pin "C7") (pinfunction "VSS_C7") (pintype "passive"))
      (node (ref "D3") (pin "D14") (pinfunction "VSS_D14") (pintype "passive"))
      (node (ref "D3") (pin "D4") (pinfunction "VSS_D4") (pintype "passive"))
      (node (ref "D3") (pin "G10") (pinfunction "VSS_G10") (pintype "power_in"))
      (node (ref "D3") (pin "G11") (pinfunction "VSS_G11") (pintype "power_in"))
      (node (ref "D3") (pin "G15") (pinfunction "VSS_G15") (pintype "power_in"))
      (node (ref "D3") (pin "G3") (pinfunction "VSS_G3") (pintype "passive"))
      (node (ref "D3") (pin "G7") (pinfunction "VSS_G7") (pintype "passive"))
      (node (ref "D3") (pin "G8") (pinfunction "VSS_G8") (pintype "power_in"))
      (node (ref "D3") (pin "G9") (pinfunction "VSS_G9") (pintype "power_in"))
      (node (ref "D3") (pin "H11") (pinfunction "VSS_H11") (pintype "power_in"))
      (node (ref "D3") (pin "H7") (pinfunction "VSS_H7") (pintype "power_in"))
      (node (ref "D3") (pin "J11") (pinfunction "VSS_J11") (pintype "power_in"))
      (node (ref "D3") (pin "J7") (pinfunction "VSS_J7") (pintype "power_in"))
      (node (ref "D3") (pin "K11") (pinfunction "VSS_K11") (pintype "power_in"))
      (node (ref "D3") (pin "K7") (pinfunction "VSS_K7") (pintype "power_in"))
      (node (ref "D3") (pin "L10") (pinfunction "VSS_L10") (pintype "power_in"))
      (node (ref "D3") (pin "L11") (pinfunction "VSS_L11") (pintype "power_in"))
      (node (ref "D3") (pin "L15") (pinfunction "VSS_L15") (pintype "power_in"))
      (node (ref "D3") (pin "L3") (pinfunction "VSS_L3") (pintype "power_in"))
      (node (ref "D3") (pin "L7") (pinfunction "VSS_L7") (pintype "power_in"))
      (node (ref "D3") (pin "L8") (pinfunction "VSS_L8") (pintype "power_in"))
      (node (ref "D3") (pin "L9") (pinfunction "VSS_L9") (pintype "power_in"))
      (node (ref "D3") (pin "P13") (pinfunction "VREFL_P13") (pintype "passive"))
      (node (ref "D3") (pin "P14") (pinfunction "VSS_P14") (pintype "power_in"))
      (node (ref "D3") (pin "P4") (pinfunction "VSS_P4") (pintype "power_in"))
      (node (ref "D3") (pin "R1") (pinfunction "DCDC_GND_R1") (pintype "power_in"))
      (node (ref "D3") (pin "R11") (pinfunction "VSS_R11") (pintype "power_in"))
      (node (ref "D3") (pin "R2") (pinfunction "DCDC_GND_R2") (pintype "power_in"))
      (node (ref "D3") (pin "R7") (pinfunction "VSS_R7") (pintype "power_in"))
      (node (ref "D3") (pin "R8") (pinfunction "VSS_R8") (pintype "power_in"))
      (node (ref "D3") (pin "T11") (pinfunction "VSS_T11") (pintype "power_in"))
      (node (ref "D3") (pin "U1") (pinfunction "VSS_U1") (pintype "power_in"))
      (node (ref "D3") (pin "U11") (pinfunction "VSS_U11") (pintype "power_in"))
      (node (ref "D3") (pin "U17") (pinfunction "VSS_U17") (pintype "power_in"))
      (node (ref "D4") (pin "2") (pinfunction "GND_2") (pintype "passive"))
      (node (ref "D5") (pin "2") (pinfunction "GND_2") (pintype "passive"))
      (node (ref "D7") (pin "11") (pinfunction "PGND_11") (pintype "passive"))
      (node (ref "D7") (pin "3") (pinfunction "PGND_3") (pintype "passive"))
      (node (ref "D7") (pin "9") (pinfunction "GND_9") (pintype "passive"))
      (node (ref "D8") (pin "2") (pinfunction "GND_2") (pintype "passive"))
      (node (ref "R16") (pin "2") (pinfunction "2_2") (pintype "passive"))
      (node (ref "R18") (pin "2") (pinfunction "2_2") (pintype "passive"))
      (node (ref "R19") (pin "1") (pinfunction "1_1") (pintype "passive"))
      (node (ref "R25") (pin "1") (pinfunction "1_1") (pintype "passive"))
      (node (ref "VT4") (pin "S") (pinfunction "S_S") (pintype "passive"))
      (node (ref "X10") (pin "A1") (pinfunction "A1_A1") (pintype "power_in"))
      (node (ref "X10") (pin "B1") (pinfunction "B1_B1") (pintype "power_in"))
    )
    (net (code "13") (name "Net-(C36-Pad2)") (class "Default")
      (node (ref "C36") (pin "2") (pinfunction "2_2") (pintype "passive"))
      (node (ref "C37") (pin "2") (pinfunction "2_2") (pintype "passive"))
      (node (ref "L3") (pin "2") (pinfunction "2_2") (pintype "passive"))
      (node (ref "R13") (pin "1") (pinfunction "1_1") (pintype "passive"))
    )
    (net (code "14") (name "Net-(C41-Pad2)") (class "Default")
      (node (ref "C41") (pin "2") (pinfunction "2_2") (pintype "passive"))
      (node (ref "C42") (pin "2") (pinfunction "2_2") (pintype "passive"))
      (node (ref "D3") (pin "R4") (pinfunction "VPMC_R4") (pintype "power_in"))
      (node (ref "D3") (pin "T7") (pinfunction "VPMC_T7") (pintype "power_in"))
      (node (ref "D3") (pin "U7") (pinfunction "VPMC_U7") (pintype "power_in"))
      (node (ref "R15") (pin "1") (pinfunction "1_1") (pintype "passive"))
    )
    (net (code "15") (name "Net-(D3G-DCDC_LP-PadT1)") (class "Default")
      (node (ref "D3") (pin "T1") (pinfunction "DCDC_LP_T1") (pintype "power_in"))
      (node (ref "D3") (pin "T2") (pinfunction "DCDC_LP_T2") (pintype "power_in"))
      (node (ref "L2") (pin "2") (pinfunction "2_2") (pintype "passive"))
    )
    (net (code "16") (name "Net-(D3G-DCDC_PSW)") (class "Default")
      (node (ref "C20") (pin "2") (pinfunction "2_2") (pintype "passive"))
      (node (ref "C21") (pin "2") (pinfunction "2_2") (pintype "passive"))
      (node (ref "C22") (pin "2") (pinfunction "2_2") (pintype "passive"))
      (node (ref "D3") (pin "T3") (pinfunction "DCDC_PSW_T3") (pintype "passive"))
      (node (ref "D3") (pin "U2") (pinfunction "DCDC_IN_U2") (pintype "power_in"))
      (node (ref "D3") (pin "U3") (pinfunction "DCDC_IN_U3") (pintype "power_in"))
      (node (ref "R11") (pin "1") (pinfunction "1_1") (pintype "passive"))
    )
    (net (code "17") (name "Net-(D3G-VANA)") (class "Default")
      (node (ref "C38") (pin "2") (pinfunction "2_2") (pintype "passive"))
      (node (ref "D3") (pin "N12") (pinfunction "VANA_N12") (pintype "power_in"))
      (node (ref "L3") (pin "1") (pinfunction "1_1") (pintype "passive"))
    )
    (net (code "18") (name "Net-(D3G-VDD_BATCAP)") (class "Default")
      (node (ref "C49") (pin "2") (pinfunction "2_2") (pintype "passive"))
      (node (ref "C50") (pin "2") (pinfunction "2_2") (pintype "passive"))
      (node (ref "D3") (pin "M8") (pinfunction "VDD_BATCAP_M8") (pintype "passive"))
    )
    (net (code "19") (name "Net-(D3G-VDD_OTPCAP)") (class "Default")
      (node (ref "C43") (pin "2") (pinfunction "2_2") (pintype "passive"))
      (node (ref "C44") (pin "2") (pinfunction "2_2") (pintype "passive"))
      (node (ref "D3") (pin "M7") (pinfunction "VDD_OTPCAP_M7") (pintype "passive"))
    )
    (net (code "20") (name "Net-(D3G-VDD_PMCCAP)") (class "Default")
      (node (ref "C56") (pin "2") (pinfunction "2_2") (pintype "passive"))
      (node (ref "C57") (pin "2") (pinfunction "2_2") (pintype "passive"))
      (node (ref "D3") (pin "M9") (pinfunction "VDD_PMCCAP_M9") (pintype "passive"))
    )
    (net (code "21") (name "Net-(D5-PROG)") (class "Default")
      (node (ref "D5") (pin "6") (pinfunction "PROG_6") (pintype "passive"))
      (node (ref "R19") (pin "2") (pinfunction "2_2") (pintype "passive"))
    )
    (net (code "22") (name "Net-(D6-GND)") (class "Default")
      (node (ref "C58") (pin "1") (pinfunction "1_1") (pintype "passive"))
      (node (ref "D6") (pin "6") (pinfunction "GND_6") (pintype "passive"))
      (node (ref "VT5") (pin "S") (pinfunction "S_S") (pintype "passive"))
      (node (ref "X11") (pin "2") (pinfunction "2_2") (pintype "passive"))
      (node (ref "X12") (pin "2") (pinfunction "2_2") (pintype "passive"))
    )
    (net (code "23") (name "Net-(D6-OC)") (class "Default")
      (node (ref "D6") (pin "3") (pinfunction "OC_3") (pintype "passive"))
      (node (ref "R21") (pin "1") (pinfunction "1_1") (pintype "passive"))
      (node (ref "VT4") (pin "G") (pinfunction "G_G") (pintype "passive"))
    )
    (net (code "24") (name "Net-(D6-OD)") (class "Default")
      (node (ref "D6") (pin "1") (pinfunction "OD_1") (pintype "passive"))
      (node (ref "VT5") (pin "G") (pinfunction "G_G") (pintype "passive"))
    )
    (net (code "25") (name "Net-(D6-VCC)") (class "Default")
      (node (ref "C58") (pin "2") (pinfunction "2_2") (pintype "passive"))
      (node (ref "D6") (pin "5") (pinfunction "VCC_5") (pintype "passive"))
      (node (ref "R20") (pin "2") (pinfunction "2_2") (pintype "passive"))
    )
    (net (code "26") (name "Net-(D6-VM)") (class "Default")
      (node (ref "D6") (pin "2") (pinfunction "VM_2") (pintype "passive"))
      (node (ref "R21") (pin "2") (pinfunction "2_2") (pintype "passive"))
    )
    (net (code "27") (name "Net-(D7-EN)") (class "Default")
      (node (ref "C73") (pin "2") (pinfunction "2_2") (pintype "passive"))
      (node (ref "D7") (pin "6") (pinfunction "EN_6") (pintype "passive"))
      (node (ref "D7") (pin "7") (pinfunction "PS/SYNC_7") (pintype "passive"))
      (node (ref "D7") (pin "8") (pinfunction "VINA_8") (pintype "passive"))
      (node (ref "R22") (pin "2") (pinfunction "2_2") (pintype "passive"))
    )
    (net (code "28") (name "Net-(D7-L1)") (class "Default")
      (node (ref "D7") (pin "4") (pinfunction "L1_4") (pintype "passive"))
      (node (ref "L4") (pin "2") (pinfunction "2_2") (pintype "passive"))
    )
    (net (code "29") (name "Net-(D7-L2)") (class "Default")
      (node (ref "D7") (pin "2") (pinfunction "L2_2") (pintype "passive"))
      (node (ref "L4") (pin "1") (pinfunction "1_1") (pintype "passive"))
    )
    (net (code "30") (name "Net-(D8-EN)") (class "Default")
      (node (ref "C74") (pin "2") (pinfunction "2_2") (pintype "passive"))
      (node (ref "D8") (pin "3") (pinfunction "EN_3") (pintype "passive"))
      (node (ref "R23") (pin "1") (pinfunction "1_1") (pintype "passive"))
    )
    (net (code "31") (name "Net-(D8-NC{slash}FB)") (class "Default")
      (node (ref "D8") (pin "4") (pinfunction "NC/FB_4") (pintype "passive"))
      (node (ref "R24") (pin "1") (pinfunction "1_1") (pintype "passive"))
      (node (ref "R25") (pin "2") (pinfunction "2_2") (pintype "passive"))
    )
    (net (code "32") (name "Net-(R16-Pad1)") (class "Default")
      (node (ref "R16") (pin "1") (pinfunction "1_1") (pintype "passive"))
      (node (ref "X10") (pin "A5") (pinfunction "A5_A5") (pintype "power_in"))
    )
    (net (code "33") (name "Net-(R18-Pad1)") (class "Default")
      (node (ref "R18") (pin "1") (pinfunction "1_1") (pintype "passive"))
      (node (ref "X10") (pin "B5") (pinfunction "B5_B5") (pintype "power_in"))
    )
    (net (code "34") (name "Net-(VD11-Kathode)") (class "Default")
      (node (ref "R14") (pin "2") (pinfunction "2_2") (pintype "passive"))
      (node (ref "VD11") (pin "K") (pinfunction "Kathode_K") (pintype "passive"))
    )
    (net (code "35") (name "Net-(VD12-Kathode)") (class "Default")
      (node (ref "R17") (pin "2") (pinfunction "2_2") (pintype "passive"))
      (node (ref "VD12") (pin "K") (pinfunction "Kathode_K") (pintype "passive"))
    )
    (net (code "36") (name "Net-(VT4-PadD)") (class "Default")
      (node (ref "VT4") (pin "D") (pinfunction "D_D") (pintype "passive"))
      (node (ref "VT5") (pin "D") (pinfunction "D_D") (pintype "passive"))
    )
    (net (code "37") (name "VDD_1V0") (class "Default")
      (node (ref "C23") (pin "2") (pinfunction "2_2") (pintype "passive"))
      (node (ref "C24") (pin "2") (pinfunction "2_2") (pintype "passive"))
      (node (ref "C25") (pin "2") (pinfunction "2_2") (pintype "passive"))
      (node (ref "C26") (pin "2") (pinfunction "2_2") (pintype "passive"))
      (node (ref "D3") (pin "R3") (pinfunction "DCDC_SNS_R3") (pintype "passive"))
      (node (ref "L2") (pin "1") (pinfunction "1_1") (pintype "passive"))
      (node (ref "R12") (pin "2") (pinfunction "2_2") (pintype "passive"))
    )
    (net (code "38") (name "VDD_SOC") (class "Default")
      (node (ref "C27") (pin "2") (pinfunction "2_2") (pintype "passive"))
      (node (ref "C28") (pin "2") (pinfunction "2_2") (pintype "passive"))
      (node (ref "C29") (pin "2") (pinfunction "2_2") (pintype "passive"))
      (node (ref "C30") (pin "2") (pinfunction "2_2") (pintype "passive"))
      (node (ref "C31") (pin "2") (pinfunction "2_2") (pintype "passive"))
      (node (ref "C32") (pin "2") (pinfunction "2_2") (pintype "passive"))
      (node (ref "C33") (pin "2") (pinfunction "2_2") (pintype "passive"))
      (node (ref "C34") (pin "2") (pinfunction "2_2") (pintype "passive"))
      (node (ref "C35") (pin "2") (pinfunction "2_2") (pintype "passive"))
      (node (ref "C40") (pin "2") (pinfunction "2_2") (pintype "passive"))
      (node (ref "D3") (pin "H10") (pinfunction "VDD_SOC_H10") (pintype "power_in"))
      (node (ref "D3") (pin "H8") (pinfunction "VDD_SOC_H8") (pintype "power_in"))
      (node (ref "D3") (pin "H9") (pinfunction "VDD_SOC_H9") (pintype "power_in"))
      (node (ref "D3") (pin "J10") (pinfunction "VDD_SOC_J10") (pintype "power_in"))
      (node (ref "D3") (pin "J8") (pinfunction "VDD_SOC_J8") (pintype "power_in"))
      (node (ref "D3") (pin "J9") (pinfunction "VDD_SOC_J9") (pintype "power_in"))
      (node (ref "D3") (pin "K10") (pinfunction "VDD_USB_K10") (pintype "power_in"))
      (node (ref "D3") (pin "K8") (pinfunction "VDD_SOC_K8") (pintype "power_in"))
      (node (ref "D3") (pin "K9") (pinfunction "VDD_SOC_K9") (pintype "power_in"))
      (node (ref "R12") (pin "1") (pinfunction "1_1") (pintype "passive"))
    )
    (net (code "39") (name "unconnected-(D3J-USB0_DP-PadU12)") (class "Default")
      (node (ref "D3") (pin "U12") (pinfunction "USB0_DP_U12") (pintype "passive"))
    )
    (net (code "40") (name "unconnected-(D3J-USB1_DP-PadU13)") (class "Default")
      (node (ref "D3") (pin "U13") (pinfunction "USB1_DP_U13") (pintype "passive"))
    )
    (net (code "41") (name "unconnected-(D3J-USB1_VBUS-PadR13)") (class "Default")
      (node (ref "D3") (pin "R13") (pinfunction "USB1_VBUS_R13") (pintype "passive"))
    )
    (net (code "42") (name "unconnected-(D6-TD-Pad4)") (class "Default")
      (node (ref "D6") (pin "4") (pinfunction "TD_4") (pintype "passive"))
    )
    (net (code "43") (name "unconnected-(X10-PadA8)") (class "Default")
      (node (ref "X10") (pin "A8") (pinfunction "A8_A8") (pintype "power_in"))
    )
    (net (code "44") (name "unconnected-(X10-PadB8)") (class "Default")
      (node (ref "X10") (pin "B8") (pinfunction "B8_B8") (pintype "power_in"))
    )
  )
)
